# Battery_Indicator.net
KiCad netlist of a schematic drawn in EAGLE
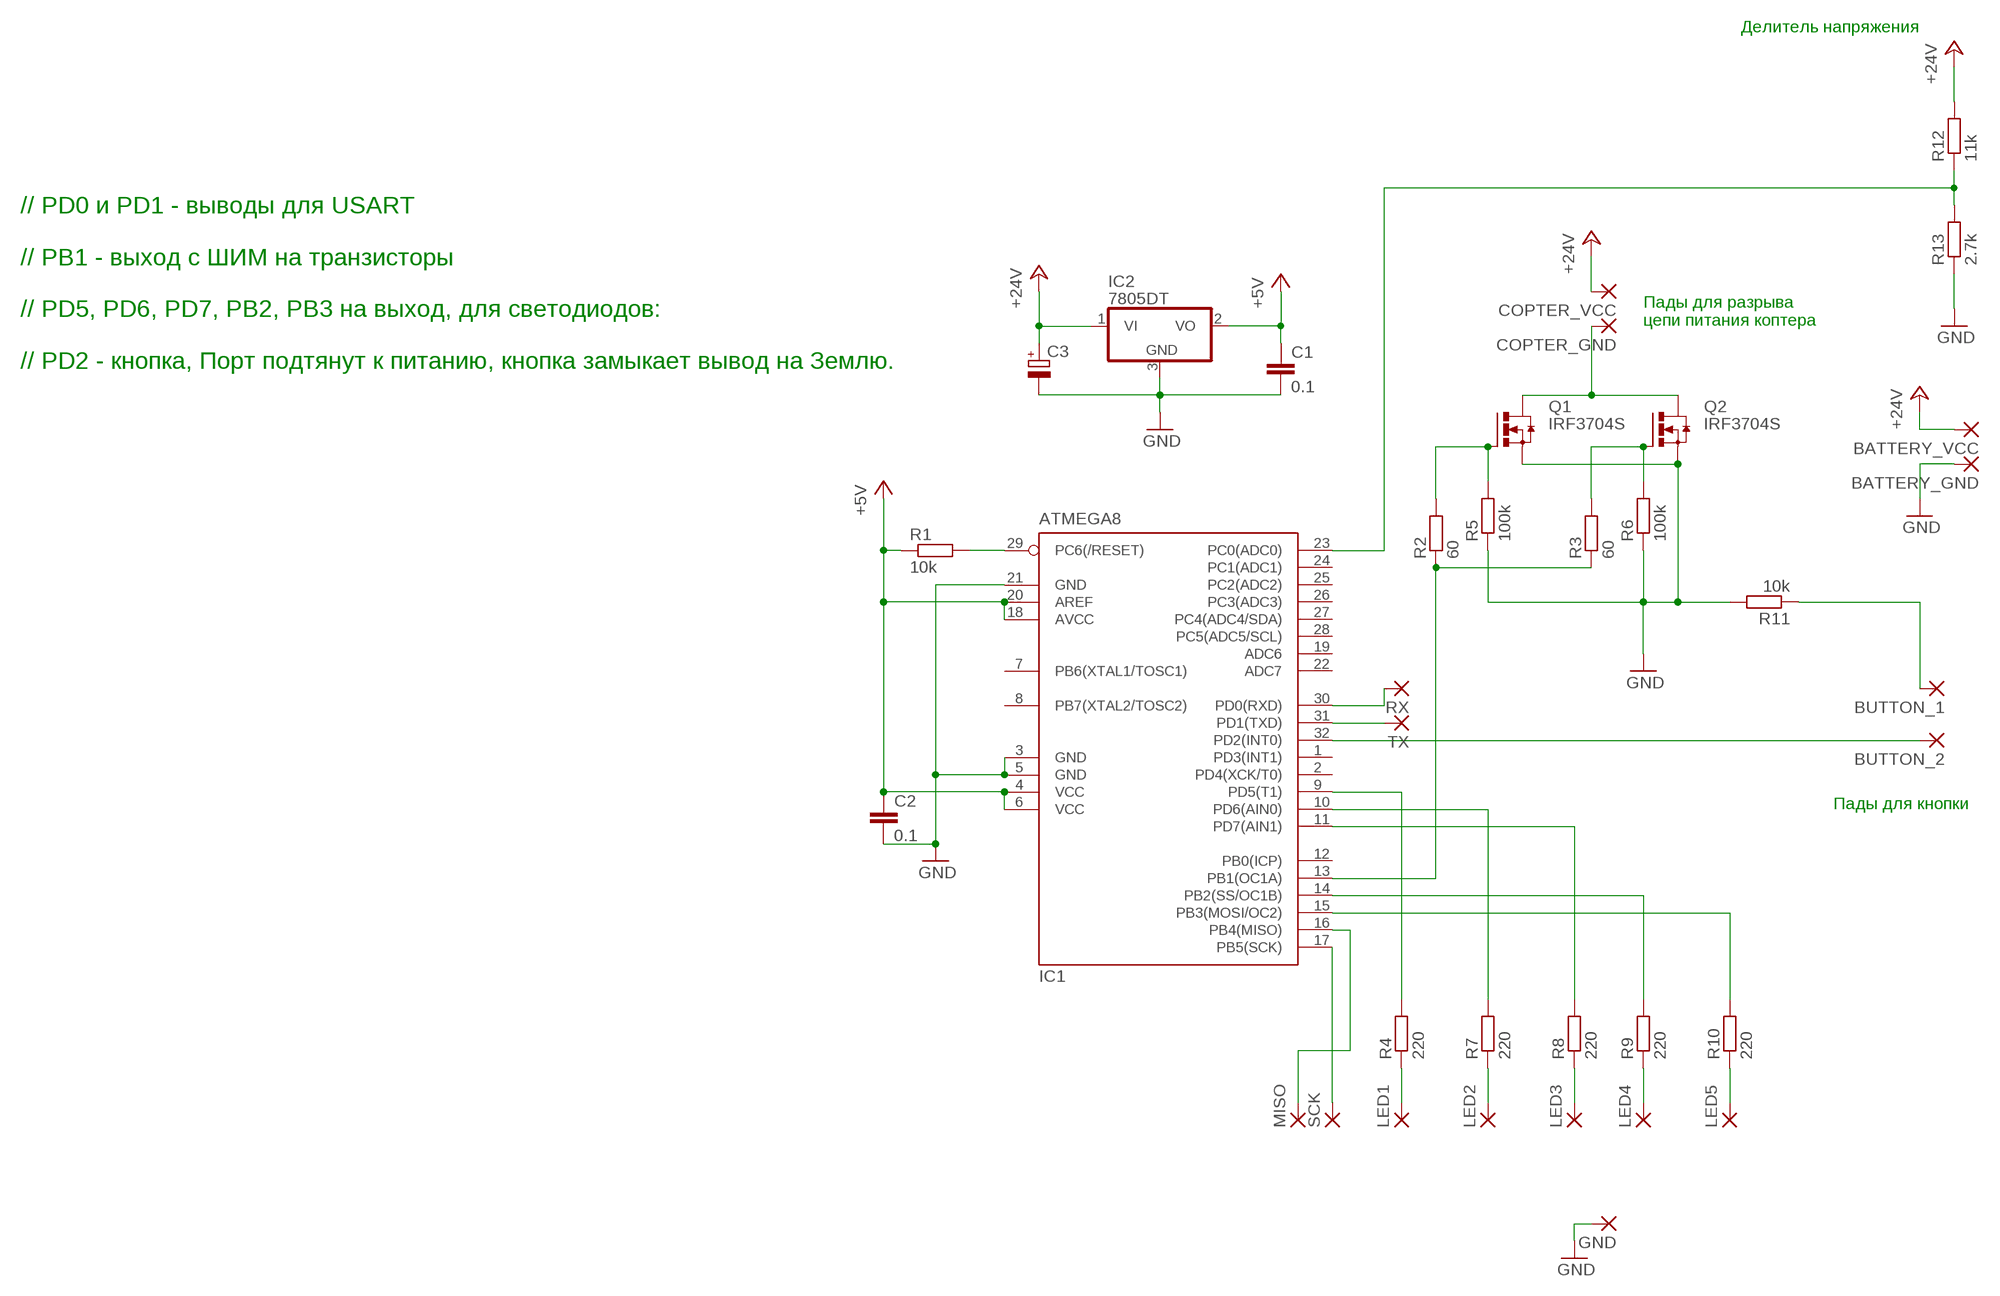
[diagram p0: schematic, sheet 1]

(export (version "E")
  (design (tool "Eeschema 10.0.6"))
  (components
    (comp (ref "BATTERY_GND")
      (value "3,81/1,4")
      (footprint "eagle-import:3,81_1,4")
      (libsource (lib "eagle-import") (part "3,81/1,4"))
    )
    (comp (ref "BATTERY_VCC")
      (value "3,81/1,4")
      (footprint "eagle-import:3,81_1,4")
      (libsource (lib "eagle-import") (part "3,81/1,4"))
    )
    (comp (ref "BUTTON_1")
      (value "SMD2")
      (footprint "eagle-import:SMD1,27-2,54")
      (libsource (lib "eagle-import") (part "SMD2"))
    )
    (comp (ref "BUTTON_2")
      (value "SMD2")
      (footprint "eagle-import:SMD1,27-2,54")
      (libsource (lib "eagle-import") (part "SMD2"))
    )
    (comp (ref "C1")
      (value "0.1")
      (footprint "eagle-import:C0805")
      (libsource (lib "eagle-import") (part "C-EUC0805"))
    )
    (comp (ref "C2")
      (value "0.1")
      (footprint "eagle-import:C0805")
      (libsource (lib "eagle-import") (part "C-EUC0805"))
    )
    (comp (ref "C3")
      (value "CPOL-EUSMCD")
      (footprint "eagle-import:SMC_D")
      (libsource (lib "eagle-import") (part "CPOL-EUSMCD"))
    )
    (comp (ref "COPTER_GND")
      (value "3,81/1,4")
      (footprint "eagle-import:3,81_1,4")
      (libsource (lib "eagle-import") (part "3,81/1,4"))
    )
    (comp (ref "COPTER_VCC")
      (value "3,81/1,4")
      (footprint "eagle-import:3,81_1,4")
      (libsource (lib "eagle-import") (part "3,81/1,4"))
    )
    (comp (ref "GND")
      (value "SMD2")
      (footprint "eagle-import:SMD1,27-2,54")
      (libsource (lib "eagle-import") (part "SMD2"))
    )
    (comp (ref "IC1")
      (value "ATMEGA8")
      (footprint "eagle-import:TQFP32-08")
      (fields (field (name "MPN") "ATMEGA8-16AU"))
      (libsource (lib "eagle-import") (part "MEGA8-AI"))
    )
    (comp (ref "IC2")
      (value "7805DT")
      (footprint "eagle-import:TO252")
      (libsource (lib "eagle-import") (part "78DT05"))
    )
    (comp (ref "LED1")
      (value "SMD2")
      (footprint "eagle-import:SMD1,27-2,54")
      (libsource (lib "eagle-import") (part "SMD2"))
    )
    (comp (ref "LED2")
      (value "SMD2")
      (footprint "eagle-import:SMD1,27-2,54")
      (libsource (lib "eagle-import") (part "SMD2"))
    )
    (comp (ref "LED3")
      (value "SMD2")
      (footprint "eagle-import:SMD1,27-2,54")
      (libsource (lib "eagle-import") (part "SMD2"))
    )
    (comp (ref "LED4")
      (value "SMD2")
      (footprint "eagle-import:SMD1,27-2,54")
      (libsource (lib "eagle-import") (part "SMD2"))
    )
    (comp (ref "LED5")
      (value "SMD2")
      (footprint "eagle-import:SMD1,27-2,54")
      (libsource (lib "eagle-import") (part "SMD2"))
    )
    (comp (ref "MISO")
      (value "SMD2")
      (footprint "eagle-import:SMD1,27-2,54")
      (libsource (lib "eagle-import") (part "SMD2"))
    )
    (comp (ref "Q1")
      (value "IRF3704S")
      (footprint "eagle-import:D2PACK")
      (libsource (lib "eagle-import") (part "IRF3704S"))
    )
    (comp (ref "Q2")
      (value "IRF3704S")
      (footprint "eagle-import:D2PACK")
      (libsource (lib "eagle-import") (part "IRF3704S"))
    )
    (comp (ref "R1")
      (value "10k")
      (footprint "eagle-import:R0805")
      (libsource (lib "eagle-import") (part "R-EU_R0805"))
    )
    (comp (ref "R2")
      (value "60")
      (footprint "eagle-import:R0805")
      (libsource (lib "eagle-import") (part "R-EU_R0805"))
    )
    (comp (ref "R3")
      (value "60")
      (footprint "eagle-import:R0805")
      (libsource (lib "eagle-import") (part "R-EU_R0805"))
    )
    (comp (ref "R4")
      (value "220")
      (footprint "eagle-import:R0805")
      (libsource (lib "eagle-import") (part "R-EU_R0805"))
    )
    (comp (ref "R5")
      (value "100k")
      (footprint "eagle-import:R0805")
      (libsource (lib "eagle-import") (part "R-EU_R0805"))
    )
    (comp (ref "R6")
      (value "100k")
      (footprint "eagle-import:R0805")
      (libsource (lib "eagle-import") (part "R-EU_R0805"))
    )
    (comp (ref "R7")
      (value "220")
      (footprint "eagle-import:R0805")
      (libsource (lib "eagle-import") (part "R-EU_R0805"))
    )
    (comp (ref "R8")
      (value "220")
      (footprint "eagle-import:R0805")
      (libsource (lib "eagle-import") (part "R-EU_R0805"))
    )
    (comp (ref "R9")
      (value "220")
      (footprint "eagle-import:R0805")
      (libsource (lib "eagle-import") (part "R-EU_R0805"))
    )
    (comp (ref "R10")
      (value "220")
      (footprint "eagle-import:R0805")
      (libsource (lib "eagle-import") (part "R-EU_R0805"))
    )
    (comp (ref "R11")
      (value "10k")
      (footprint "eagle-import:R0805")
      (libsource (lib "eagle-import") (part "R-EU_R0805"))
    )
    (comp (ref "R12")
      (value "11k")
      (footprint "eagle-import:R0805")
      (libsource (lib "eagle-import") (part "R-EU_R0805"))
    )
    (comp (ref "R13")
      (value "2.7k")
      (footprint "eagle-import:R0805")
      (libsource (lib "eagle-import") (part "R-EU_R0805"))
    )
    (comp (ref "RX")
      (value "SMD2")
      (footprint "eagle-import:SMD1,27-2,54")
      (libsource (lib "eagle-import") (part "SMD2"))
    )
    (comp (ref "SCK")
      (value "SMD2")
      (footprint "eagle-import:SMD1,27-2,54")
      (libsource (lib "eagle-import") (part "SMD2"))
    )
    (comp (ref "TX")
      (value "SMD2")
      (footprint "eagle-import:SMD1,27-2,54")
      (libsource (lib "eagle-import") (part "SMD2"))
    )
  )
  (nets
    (net (code "1") (name "+5V") (class "Default")
      (node (ref "C1") (pin "1") (pinfunction "1_1") (pintype "passive"))
      (node (ref "C2") (pin "1") (pinfunction "1_1") (pintype "passive"))
      (node (ref "IC1") (pin "18") (pinfunction "AVCC_18") (pintype "power_in"))
      (node (ref "IC1") (pin "20") (pinfunction "AREF_20") (pintype "passive"))
      (node (ref "IC1") (pin "4") (pinfunction "VCC_4") (pintype "power_in"))
      (node (ref "IC1") (pin "6") (pinfunction "VCC_6") (pintype "power_in"))
      (node (ref "IC2") (pin "2") (pinfunction "VO_2") (pintype "passive"))
      (node (ref "R1") (pin "1") (pinfunction "1_1") (pintype "passive"))
    )
    (net (code "2") (name "+24V") (class "Default")
      (node (ref "BATTERY_VCC") (pin "1") (pinfunction "P_1") (pintype "passive"))
      (node (ref "C3") (pin "+") (pinfunction "+_+") (pintype "passive"))
      (node (ref "COPTER_VCC") (pin "1") (pinfunction "P_1") (pintype "passive"))
      (node (ref "IC2") (pin "1") (pinfunction "VI_1") (pintype "input"))
      (node (ref "R12") (pin "2") (pinfunction "2_2") (pintype "passive"))
    )
    (net (code "3") (name "GND") (class "Default")
      (node (ref "BATTERY_GND") (pin "1") (pinfunction "P_1") (pintype "passive"))
      (node (ref "C1") (pin "2") (pinfunction "2_2") (pintype "passive"))
      (node (ref "C2") (pin "2") (pinfunction "2_2") (pintype "passive"))
      (node (ref "C3") (pin "-") (pinfunction "-_-") (pintype "passive"))
      (node (ref "GND") (pin "1") (pinfunction "P_1") (pintype "passive"))
      (node (ref "IC1") (pin "21") (pinfunction "GND_21") (pintype "power_in"))
      (node (ref "IC1") (pin "3") (pinfunction "GND_3") (pintype "power_in"))
      (node (ref "IC1") (pin "5") (pinfunction "GND_5") (pintype "power_in"))
      (node (ref "IC2") (pin "3") (pinfunction "GND_3") (pintype "passive"))
      (node (ref "Q1") (pin "3") (pinfunction "S_3") (pintype "passive"))
      (node (ref "Q2") (pin "3") (pinfunction "S_3") (pintype "passive"))
      (node (ref "R11") (pin "2") (pinfunction "2_2") (pintype "passive"))
      (node (ref "R13") (pin "1") (pinfunction "1_1") (pintype "passive"))
      (node (ref "R5") (pin "1") (pinfunction "1_1") (pintype "passive"))
      (node (ref "R6") (pin "1") (pinfunction "1_1") (pintype "passive"))
    )
    (net (code "4") (name "Net-(BUTTON_1-P)") (class "Default")
      (node (ref "BUTTON_1") (pin "1") (pinfunction "P_1") (pintype "passive"))
      (node (ref "R11") (pin "1") (pinfunction "1_1") (pintype "passive"))
    )
    (net (code "5") (name "Net-(BUTTON_2-P)") (class "Default")
      (node (ref "BUTTON_2") (pin "1") (pinfunction "P_1") (pintype "passive"))
      (node (ref "IC1") (pin "32") (pinfunction "PD2(INT0)_32") (pintype "bidirectional"))
    )
    (net (code "6") (name "Net-(COPTER_GND-P)") (class "Default")
      (node (ref "COPTER_GND") (pin "1") (pinfunction "P_1") (pintype "passive"))
      (node (ref "Q1") (pin "2") (pinfunction "D_2") (pintype "passive"))
      (node (ref "Q2") (pin "2") (pinfunction "D_2") (pintype "passive"))
    )
    (net (code "7") (name "Net-(IC1-PB1(OC1A))") (class "Default")
      (node (ref "IC1") (pin "13") (pinfunction "PB1(OC1A)_13") (pintype "bidirectional"))
      (node (ref "R2") (pin "1") (pinfunction "1_1") (pintype "passive"))
      (node (ref "R3") (pin "1") (pinfunction "1_1") (pintype "passive"))
    )
    (net (code "8") (name "Net-(IC1-PB2(SS{slash}OC1B))") (class "Default")
      (node (ref "IC1") (pin "14") (pinfunction "PB2(SS/OC1B)_14") (pintype "bidirectional"))
      (node (ref "R9") (pin "2") (pinfunction "2_2") (pintype "passive"))
    )
    (net (code "9") (name "Net-(IC1-PB3(MOSI{slash}OC2))") (class "Default")
      (node (ref "IC1") (pin "15") (pinfunction "PB3(MOSI/OC2)_15") (pintype "bidirectional"))
      (node (ref "R10") (pin "2") (pinfunction "2_2") (pintype "passive"))
    )
    (net (code "10") (name "Net-(IC1-PB4(MISO))") (class "Default")
      (node (ref "IC1") (pin "16") (pinfunction "PB4(MISO)_16") (pintype "bidirectional"))
      (node (ref "MISO") (pin "1") (pinfunction "P_1") (pintype "passive"))
    )
    (net (code "11") (name "Net-(IC1-PB5(SCK))") (class "Default")
      (node (ref "IC1") (pin "17") (pinfunction "PB5(SCK)_17") (pintype "bidirectional"))
      (node (ref "SCK") (pin "1") (pinfunction "P_1") (pintype "passive"))
    )
    (net (code "12") (name "Net-(IC1-PC0(ADC0))") (class "Default")
      (node (ref "IC1") (pin "23") (pinfunction "PC0(ADC0)_23") (pintype "bidirectional"))
      (node (ref "R12") (pin "1") (pinfunction "1_1") (pintype "passive"))
      (node (ref "R13") (pin "2") (pinfunction "2_2") (pintype "passive"))
    )
    (net (code "13") (name "Net-(IC1-PC6({slash}RESET))") (class "Default")
      (node (ref "IC1") (pin "29") (pinfunction "PC6(/RESET)_29") (pintype "bidirectional"))
      (node (ref "R1") (pin "2") (pinfunction "2_2") (pintype "passive"))
    )
    (net (code "14") (name "Net-(IC1-PD0(RXD))") (class "Default")
      (node (ref "IC1") (pin "30") (pinfunction "PD0(RXD)_30") (pintype "bidirectional"))
      (node (ref "RX") (pin "1") (pinfunction "P_1") (pintype "passive"))
    )
    (net (code "15") (name "Net-(IC1-PD1(TXD))") (class "Default")
      (node (ref "IC1") (pin "31") (pinfunction "PD1(TXD)_31") (pintype "bidirectional"))
      (node (ref "TX") (pin "1") (pinfunction "P_1") (pintype "passive"))
    )
    (net (code "16") (name "Net-(IC1-PD5(T1))") (class "Default")
      (node (ref "IC1") (pin "9") (pinfunction "PD5(T1)_9") (pintype "bidirectional"))
      (node (ref "R4") (pin "2") (pinfunction "2_2") (pintype "passive"))
    )
    (net (code "17") (name "Net-(IC1-PD6(AIN0))") (class "Default")
      (node (ref "IC1") (pin "10") (pinfunction "PD6(AIN0)_10") (pintype "bidirectional"))
      (node (ref "R7") (pin "2") (pinfunction "2_2") (pintype "passive"))
    )
    (net (code "18") (name "Net-(IC1-PD7(AIN1))") (class "Default")
      (node (ref "IC1") (pin "11") (pinfunction "PD7(AIN1)_11") (pintype "bidirectional"))
      (node (ref "R8") (pin "2") (pinfunction "2_2") (pintype "passive"))
    )
    (net (code "19") (name "Net-(LED1-P)") (class "Default")
      (node (ref "LED1") (pin "1") (pinfunction "P_1") (pintype "passive"))
      (node (ref "R4") (pin "1") (pinfunction "1_1") (pintype "passive"))
    )
    (net (code "20") (name "Net-(LED2-P)") (class "Default")
      (node (ref "LED2") (pin "1") (pinfunction "P_1") (pintype "passive"))
      (node (ref "R7") (pin "1") (pinfunction "1_1") (pintype "passive"))
    )
    (net (code "21") (name "Net-(LED3-P)") (class "Default")
      (node (ref "LED3") (pin "1") (pinfunction "P_1") (pintype "passive"))
      (node (ref "R8") (pin "1") (pinfunction "1_1") (pintype "passive"))
    )
    (net (code "22") (name "Net-(LED4-P)") (class "Default")
      (node (ref "LED4") (pin "1") (pinfunction "P_1") (pintype "passive"))
      (node (ref "R9") (pin "1") (pinfunction "1_1") (pintype "passive"))
    )
    (net (code "23") (name "Net-(LED5-P)") (class "Default")
      (node (ref "LED5") (pin "1") (pinfunction "P_1") (pintype "passive"))
      (node (ref "R10") (pin "1") (pinfunction "1_1") (pintype "passive"))
    )
    (net (code "24") (name "Net-(Q1-G)") (class "Default")
      (node (ref "Q1") (pin "1") (pinfunction "G_1") (pintype "passive"))
      (node (ref "R2") (pin "2") (pinfunction "2_2") (pintype "passive"))
      (node (ref "R5") (pin "2") (pinfunction "2_2") (pintype "passive"))
    )
    (net (code "25") (name "Net-(Q2-G)") (class "Default")
      (node (ref "Q2") (pin "1") (pinfunction "G_1") (pintype "passive"))
      (node (ref "R3") (pin "2") (pinfunction "2_2") (pintype "passive"))
      (node (ref "R6") (pin "2") (pinfunction "2_2") (pintype "passive"))
    )
    (net (code "26") (name "unconnected-(IC1-ADC6-Pad19)") (class "Default")
      (node (ref "IC1") (pin "19") (pinfunction "ADC6_19") (pintype "bidirectional"))
    )
    (net (code "27") (name "unconnected-(IC1-ADC7-Pad22)") (class "Default")
      (node (ref "IC1") (pin "22") (pinfunction "ADC7_22") (pintype "bidirectional"))
    )
    (net (code "28") (name "unconnected-(IC1-PB0(ICP)-Pad12)") (class "Default")
      (node (ref "IC1") (pin "12") (pinfunction "PB0(ICP)_12") (pintype "bidirectional"))
    )
    (net (code "29") (name "unconnected-(IC1-PB6(XTAL1{slash}TOSC1)-Pad7)") (class "Default")
      (node (ref "IC1") (pin "7") (pinfunction "PB6(XTAL1/TOSC1)_7") (pintype "bidirectional"))
    )
    (net (code "30") (name "unconnected-(IC1-PB7(XTAL2{slash}TOSC2)-Pad8)") (class "Default")
      (node (ref "IC1") (pin "8") (pinfunction "PB7(XTAL2/TOSC2)_8") (pintype "bidirectional"))
    )
    (net (code "31") (name "unconnected-(IC1-PC1(ADC1)-Pad24)") (class "Default")
      (node (ref "IC1") (pin "24") (pinfunction "PC1(ADC1)_24") (pintype "bidirectional"))
    )
    (net (code "32") (name "unconnected-(IC1-PC2(ADC2)-Pad25)") (class "Default")
      (node (ref "IC1") (pin "25") (pinfunction "PC2(ADC2)_25") (pintype "bidirectional"))
    )
    (net (code "33") (name "unconnected-(IC1-PC3(ADC3)-Pad26)") (class "Default")
      (node (ref "IC1") (pin "26") (pinfunction "PC3(ADC3)_26") (pintype "bidirectional"))
    )
    (net (code "34") (name "unconnected-(IC1-PC4(ADC4{slash}SDA)-Pad27)") (class "Default")
      (node (ref "IC1") (pin "27") (pinfunction "PC4(ADC4/SDA)_27") (pintype "bidirectional"))
    )
    (net (code "35") (name "unconnected-(IC1-PC5(ADC5{slash}SCL)-Pad28)") (class "Default")
      (node (ref "IC1") (pin "28") (pinfunction "PC5(ADC5/SCL)_28") (pintype "bidirectional"))
    )
    (net (code "36") (name "unconnected-(IC1-PD3(INT1)-Pad1)") (class "Default")
      (node (ref "IC1") (pin "1") (pinfunction "PD3(INT1)_1") (pintype "bidirectional"))
    )
    (net (code "37") (name "unconnected-(IC1-PD4(XCK{slash}T0)-Pad2)") (class "Default")
      (node (ref "IC1") (pin "2") (pinfunction "PD4(XCK/T0)_2") (pintype "bidirectional"))
    )
  )
)
